# SparkFun_GPS_RTK_Surveyor_-_Single_End.net
KiCad netlist of a schematic drawn in EAGLE
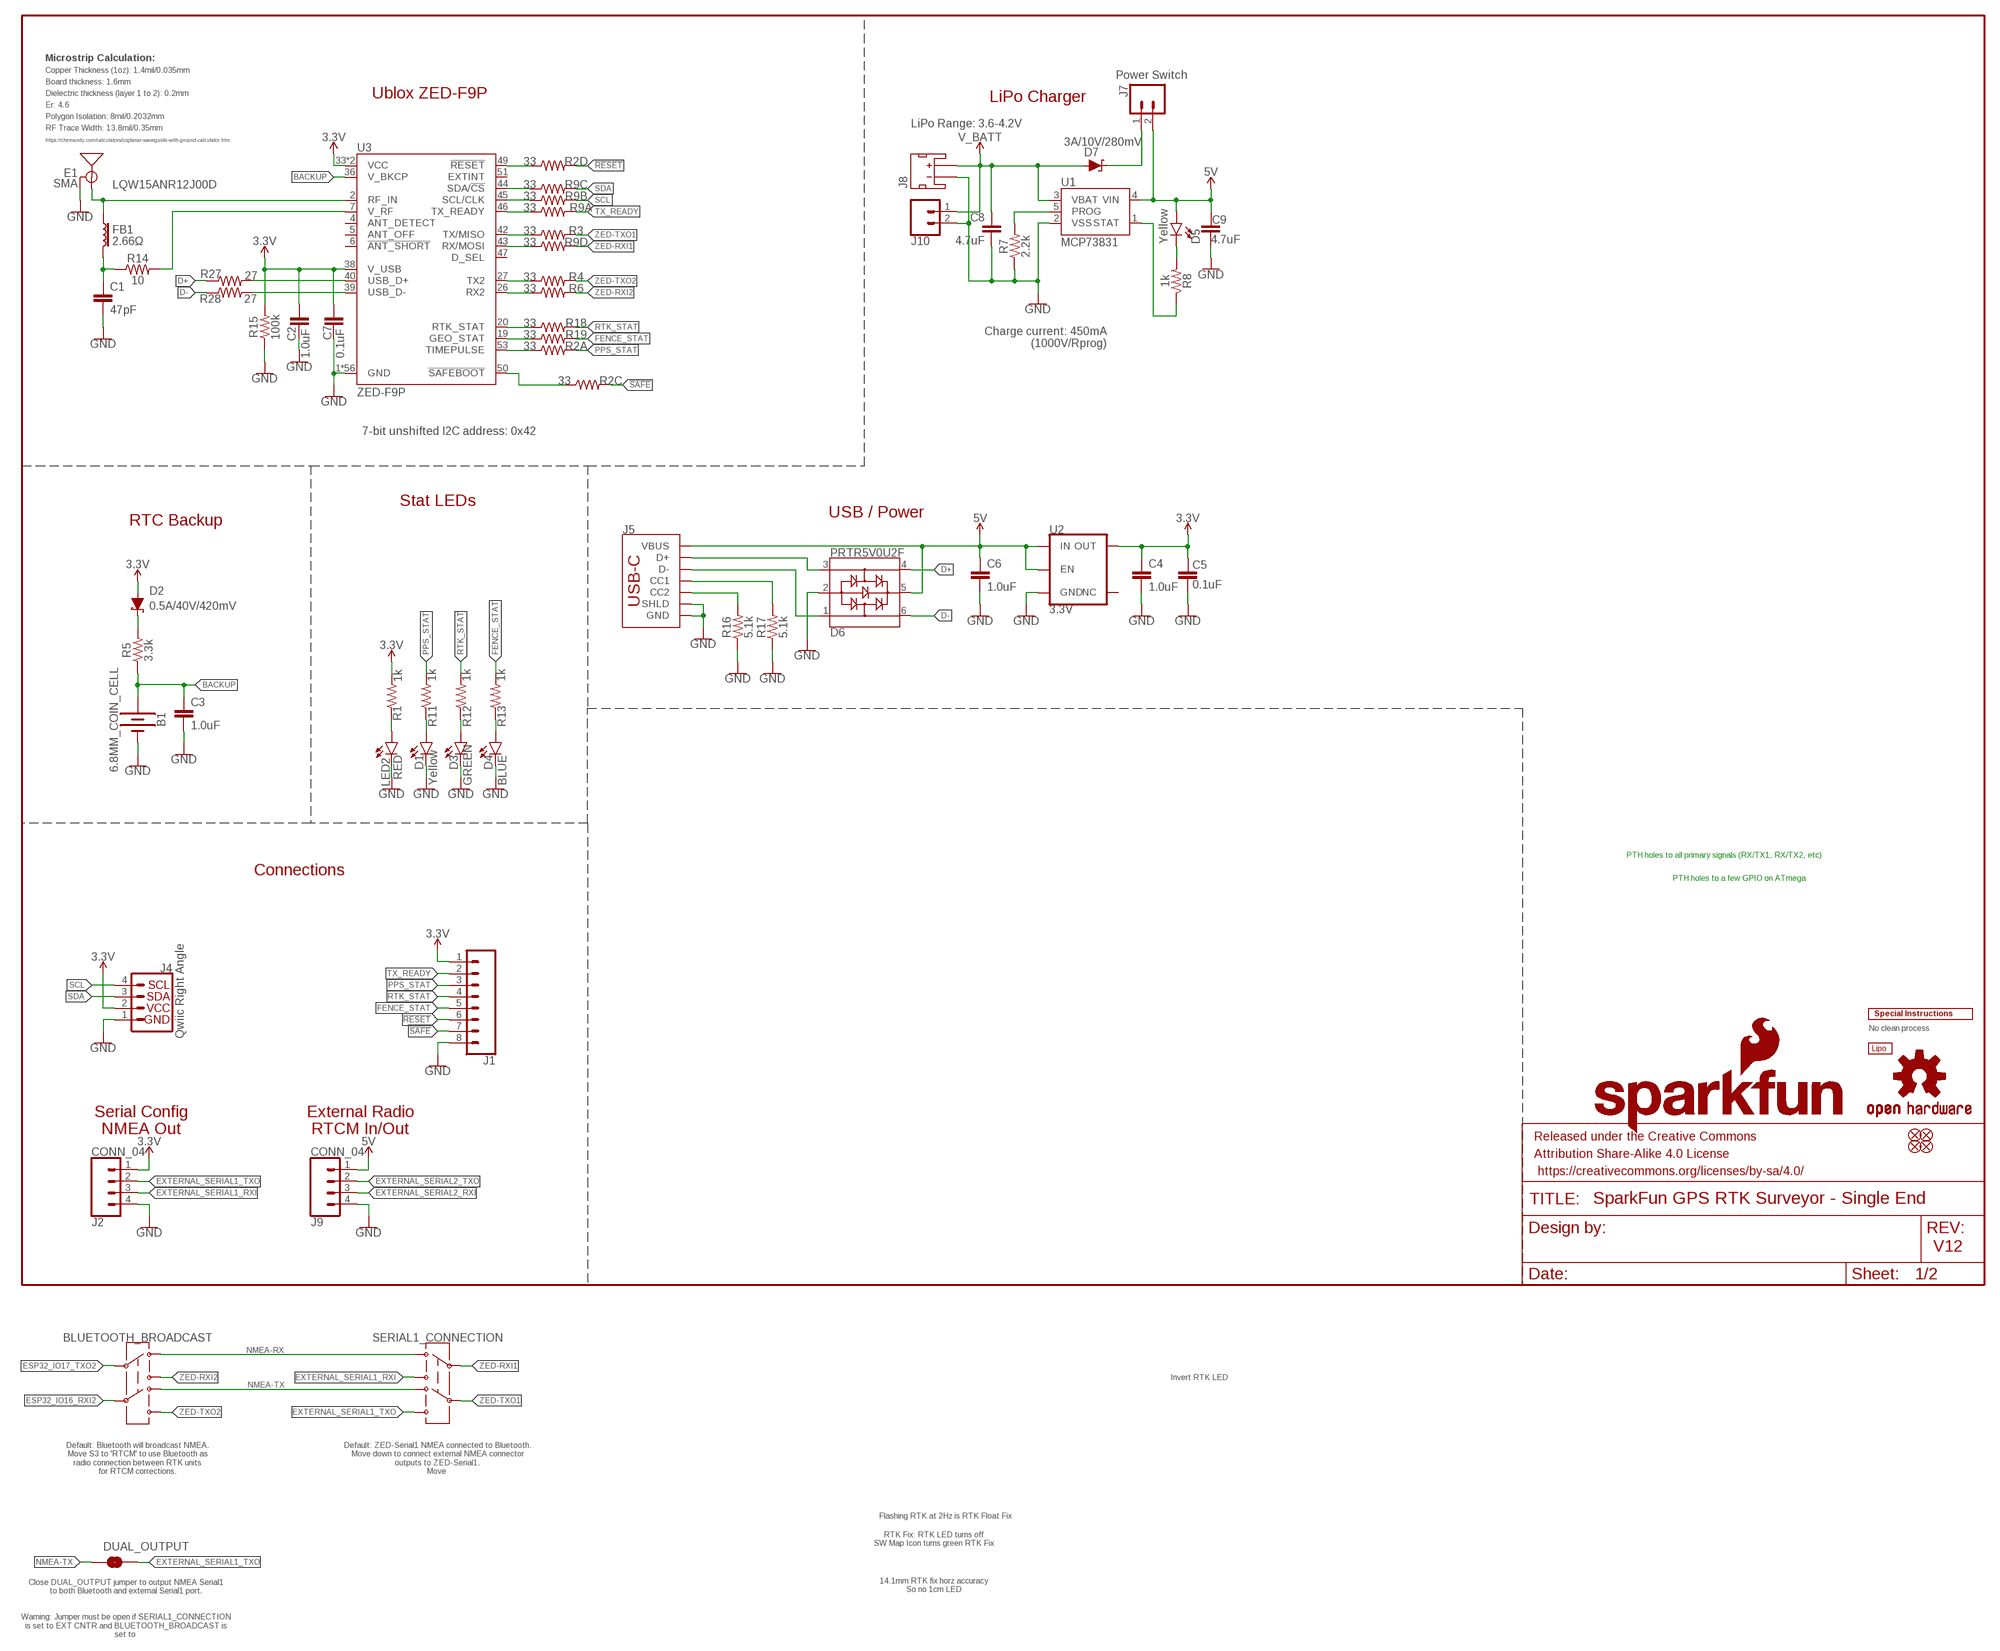
[diagram p0: schematic, sheet 1, part 1 of 2]
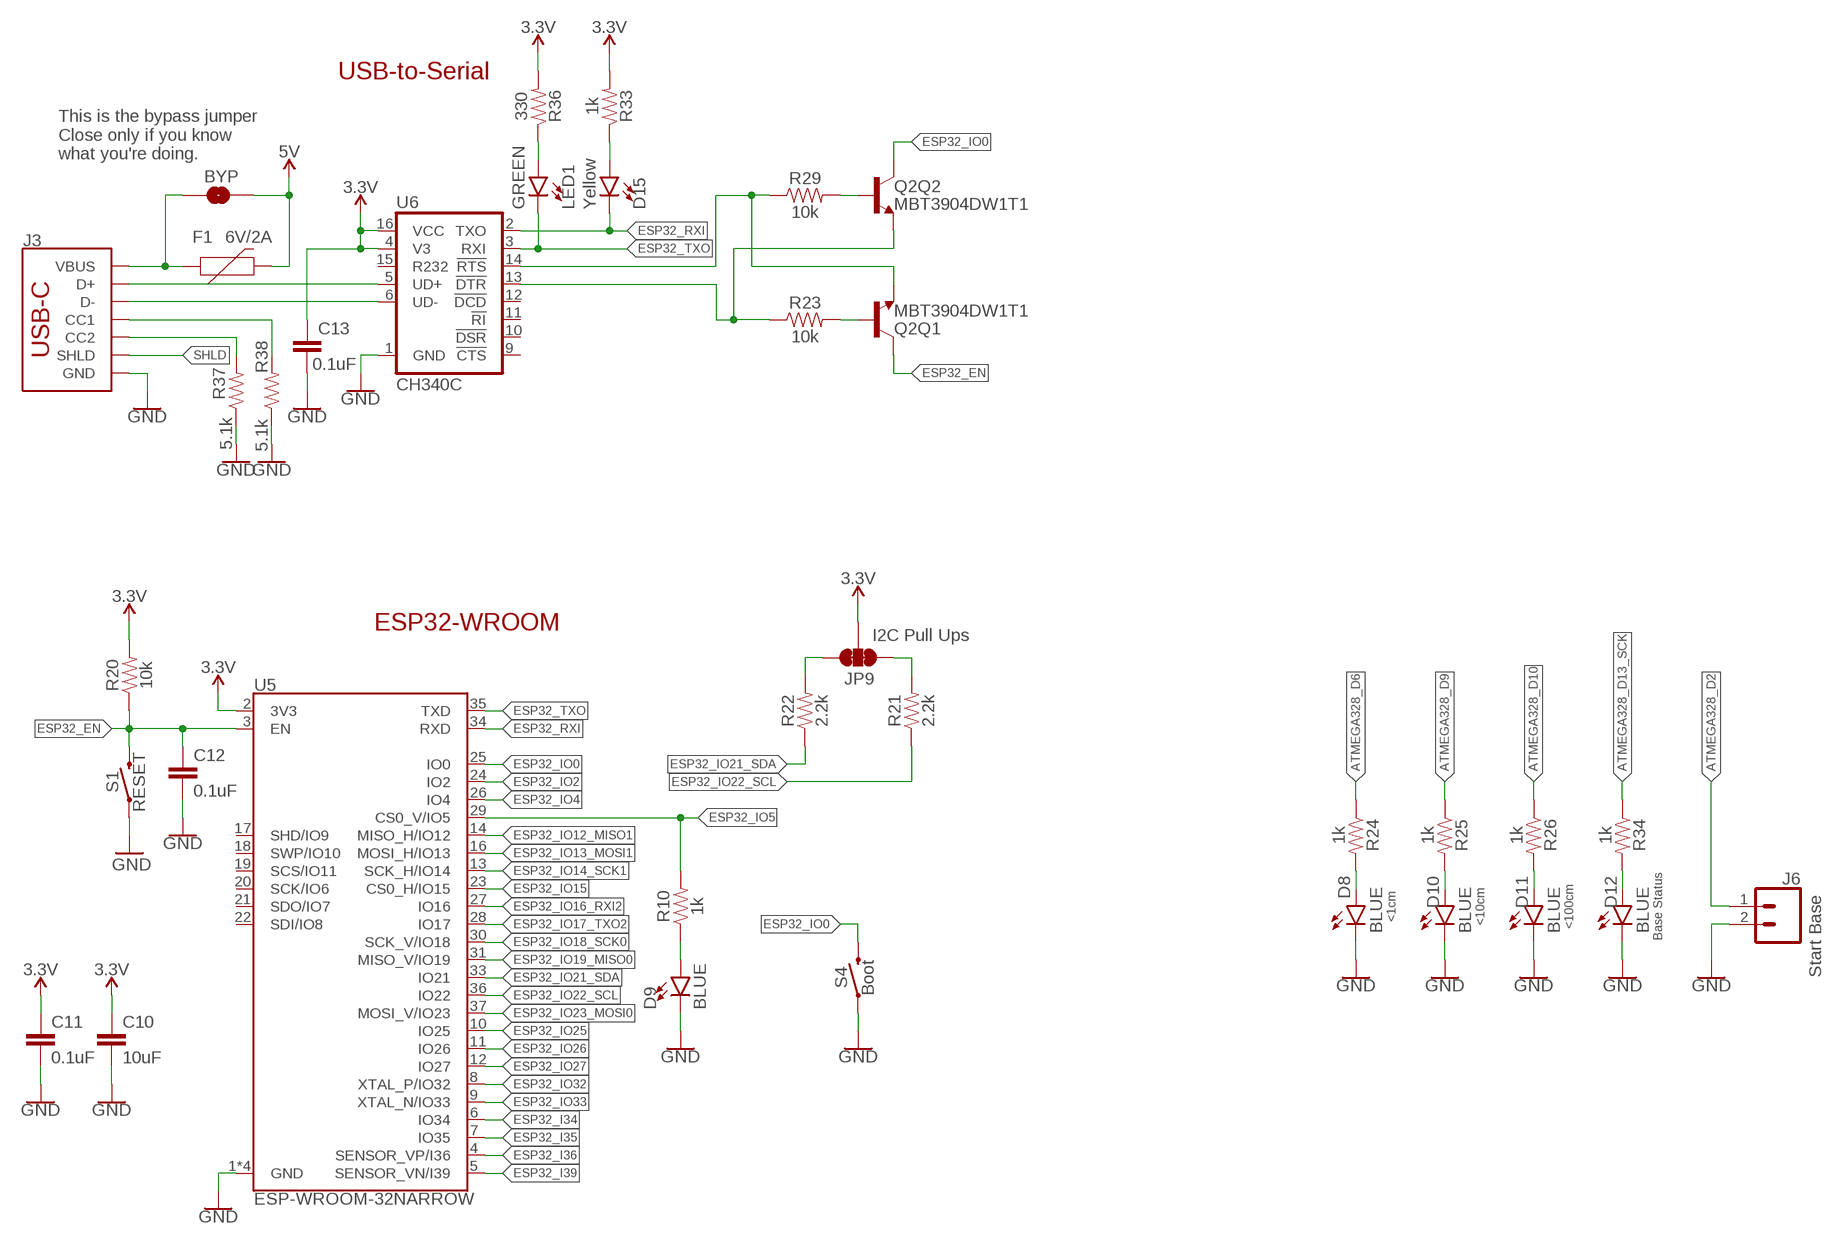
[diagram p1: schematic, sheet 1, part 2 of 2]

(export (version "E")
  (design (tool "Eeschema 10.0.6"))
  (components
    (comp (ref "B1")
      (value "6.8MM_COIN_CELL")
      (footprint "eagle-import:ML414H_IV01E")
      (libsource (lib "eagle-import") (part "ML414H_IV01E_BATTERY"))
    )
    (comp (ref "BLUETOOTH_BROADCAST")
      (value "SWITCH-DPDT-SMD-AYZ0202")
      (footprint "eagle-import:SWITCH_DPDT_SMD_AYZ0202")
      (libsource (lib "eagle-import") (part "SWITCH-DPDT-SMD-AYZ0202"))
    )
    (comp (ref "BT1")
      (value "LIPO-OUTLINE1100")
      (footprint "eagle-import:LIPO-1000")
      (libsource (lib "eagle-import") (part "LIPO-OUTLINE1100"))
    )
    (comp (ref "BYP")
      (value "JUMPER-SMT_2_NO_SILK")
      (footprint "eagle-import:SMT-JUMPER_2_NO_SILK")
      (libsource (lib "eagle-import") (part "JUMPER-SMT_2_NO_SILK"))
    )
    (comp (ref "C1")
      (value "47pF")
      (footprint "eagle-import:0402")
      (libsource (lib "eagle-import") (part "47PF-0402-25V-5%-X7R"))
    )
    (comp (ref "C2")
      (value "1.0uF")
      (footprint "eagle-import:0603")
      (libsource (lib "eagle-import") (part "1.0UF-0603-16V-10%-X7R"))
    )
    (comp (ref "C3")
      (value "1.0uF")
      (footprint "eagle-import:0603")
      (libsource (lib "eagle-import") (part "1.0UF-0603-16V-10%-X7R"))
    )
    (comp (ref "C4")
      (value "1.0uF")
      (footprint "eagle-import:0603")
      (libsource (lib "eagle-import") (part "1.0UF-0603-16V-10%-X7R"))
    )
    (comp (ref "C5")
      (value "0.1uF")
      (footprint "eagle-import:0603")
      (libsource (lib "eagle-import") (part "0.1UF-0603-25V-5%"))
    )
    (comp (ref "C6")
      (value "1.0uF")
      (footprint "eagle-import:0603")
      (libsource (lib "eagle-import") (part "1.0UF-0603-16V-10%-X7R"))
    )
    (comp (ref "C7")
      (value "0.1uF")
      (footprint "eagle-import:0603")
      (libsource (lib "eagle-import") (part "0.1UF-0603-25V-5%"))
    )
    (comp (ref "C8")
      (value "4.7uF")
      (footprint "eagle-import:0603")
      (libsource (lib "eagle-import") (part "4.7UF-0603-35V-(20%)"))
    )
    (comp (ref "C9")
      (value "4.7uF")
      (footprint "eagle-import:0603")
      (libsource (lib "eagle-import") (part "4.7UF-0603-35V-(20%)"))
    )
    (comp (ref "C10")
      (value "10uF")
      (footprint "eagle-import:0603")
      (libsource (lib "eagle-import") (part "10UF-0603-6.3V-20%"))
    )
    (comp (ref "C11")
      (value "0.1uF")
      (footprint "eagle-import:0603")
      (libsource (lib "eagle-import") (part "0.1UF-0603-25V-(+80/-20%)"))
    )
    (comp (ref "C12")
      (value "0.1uF")
      (footprint "eagle-import:0603")
      (libsource (lib "eagle-import") (part "0.1UF-0603-25V-(+80/-20%)"))
    )
    (comp (ref "C13")
      (value "0.1uF")
      (footprint "eagle-import:0603")
      (libsource (lib "eagle-import") (part "0.1UF-0603-25V-(+80/-20%)"))
    )
    (comp (ref "D1")
      (value "Yellow")
      (footprint "eagle-import:LED-0603")
      (libsource (lib "eagle-import") (part "LED-YELLOW0603"))
    )
    (comp (ref "D2")
      (value "0.5A/40V/420mV")
      (footprint "eagle-import:SOD-323")
      (libsource (lib "eagle-import") (part "DIODE-SCHOTTKY-PMEG4005EJ"))
    )
    (comp (ref "D3")
      (value "GREEN")
      (footprint "eagle-import:LED-0603")
      (libsource (lib "eagle-import") (part "LED-GREEN0603"))
    )
    (comp (ref "D4")
      (value "BLUE")
      (footprint "eagle-import:LED-0603")
      (libsource (lib "eagle-import") (part "LED-BLUE0603"))
    )
    (comp (ref "D5")
      (value "Yellow")
      (footprint "eagle-import:LED-0603")
      (libsource (lib "eagle-import") (part "LED-YELLOW0603"))
    )
    (comp (ref "D6")
      (value "PRTR5V0U2F")
      (footprint "eagle-import:SOT886")
      (libsource (lib "eagle-import") (part "PRTR5V0U2F"))
    )
    (comp (ref "D7")
      (value "3A/10V/280mV")
      (footprint "eagle-import:SOD-323")
      (libsource (lib "eagle-import") (part "DIODE-SCHOTTKY-BAT60A"))
    )
    (comp (ref "D8")
      (value "BLUE")
      (footprint "eagle-import:LED-0603")
      (libsource (lib "eagle-import") (part "LED-BLUE0603"))
    )
    (comp (ref "D9")
      (value "BLUE")
      (footprint "eagle-import:LED-0603")
      (libsource (lib "eagle-import") (part "LED-BLUE0603"))
    )
    (comp (ref "D10")
      (value "BLUE")
      (footprint "eagle-import:LED-0603")
      (libsource (lib "eagle-import") (part "LED-BLUE0603"))
    )
    (comp (ref "D11")
      (value "BLUE")
      (footprint "eagle-import:LED-0603")
      (libsource (lib "eagle-import") (part "LED-BLUE0603"))
    )
    (comp (ref "D12")
      (value "BLUE")
      (footprint "eagle-import:LED-0603")
      (libsource (lib "eagle-import") (part "LED-BLUE0603"))
    )
    (comp (ref "D15")
      (value "Yellow")
      (footprint "eagle-import:LED-0603")
      (libsource (lib "eagle-import") (part "LED-YELLOW0603"))
    )
    (comp (ref "DUAL_OUTPUT")
      (value "JUMPER-SMT_2_NO_SILK")
      (footprint "eagle-import:SMT-JUMPER_2_NO_SILK")
      (libsource (lib "eagle-import") (part "JUMPER-SMT_2_NO_SILK"))
    )
    (comp (ref "E1")
      (value "SMA")
      (footprint "eagle-import:SMA-EDGE-SMD")
      (libsource (lib "eagle-import") (part "ANTENNA-GROUNDEDEDGE_SMA_SMD"))
    )
    (comp (ref "F1")
      (value "6V/2A")
      (footprint "eagle-import:1210")
      (libsource (lib "eagle-import") (part "PPTC_6V2A"))
    )
    (comp (ref "FB1")
      (value "2.66Ω")
      (footprint "eagle-import:0402-TIGHT")
      (libsource (lib "eagle-import") (part "FERRITE_BEAD-0402-2.66OHM-1GHZ"))
    )
    (comp (ref "FRAME2")
      (value "FRAME-LEDGER")
      (footprint "eagle-import:CREATIVE_COMMONS")
      (libsource (lib "eagle-import") (part "FRAME-LEDGER"))
    )
    (comp (ref "J1")
      (value "CONN_08NO_SILK_DNP")
      (footprint "eagle-import:1X08_NO_SILK")
      (libsource (lib "eagle-import") (part "CONN_08NO_SILK_DNP"))
    )
    (comp (ref "J2")
      (value "CONN_04")
      (footprint "eagle-import:JST-4-SMD-1.25MM-LOCKING")
      (libsource (lib "eagle-import") (part "CONN_04"))
    )
    (comp (ref "J3")
      (value "USB-C")
      (footprint "eagle-import:USB-C-16P-2LAYER-PADS")
      (libsource (lib "eagle-import") (part "USB_C_2-LAYER_PADS"))
    )
    (comp (ref "J4")
      (value "Qwiic Right Angle")
      (footprint "eagle-import:JST04_1MM_RA")
      (libsource (lib "eagle-import") (part "I2C_STANDARDQWIIC"))
    )
    (comp (ref "J5")
      (value "USB_C_2-LAYER_PADS")
      (footprint "eagle-import:USB-C-16P-2LAYER-PADS")
      (libsource (lib "eagle-import") (part "USB_C_2-LAYER_PADS"))
    )
    (comp (ref "J6")
      (value "Start Base")
      (footprint "eagle-import:JST-2-SMD")
      (libsource (lib "eagle-import") (part "CONN_02-JST-2MM-SMT"))
    )
    (comp (ref "J7")
      (value "Power Switch")
      (footprint "eagle-import:JST-2-SMD")
      (libsource (lib "eagle-import") (part "CONN_02-JST-2MM-SMT"))
    )
    (comp (ref "J8")
      (value "JST_2MM_MALE")
      (footprint "eagle-import:JST-2-SMD")
      (libsource (lib "eagle-import") (part "JST_2MM_MALE"))
    )
    (comp (ref "J9")
      (value "CONN_04")
      (footprint "eagle-import:JST-4-SMD-1.25MM-LOCKING")
      (libsource (lib "eagle-import") (part "CONN_04"))
    )
    (comp (ref "J10")
      (value "CONN_021X02_NO_SILK")
      (footprint "eagle-import:1X02_NO_SILK")
      (libsource (lib "eagle-import") (part "CONN_021X02_NO_SILK"))
    )
    (comp (ref "JP9")
      (value "JUMPER-SMT_3_2-NC_TRACE_SILK")
      (footprint "eagle-import:SMT-JUMPER_3_2-NC_TRACE_SILK")
      (libsource (lib "eagle-import") (part "JUMPER-SMT_3_2-NC_TRACE_SILK"))
    )
    (comp (ref "JP21")
      (value "FIDUCIALUFIDUCIAL")
      (footprint "eagle-import:MICRO-FIDUCIAL")
      (libsource (lib "eagle-import") (part "FIDUCIALUFIDUCIAL"))
    )
    (comp (ref "JP61")
      (value "FIDUCIALUFIDUCIAL")
      (footprint "eagle-import:MICRO-FIDUCIAL")
      (libsource (lib "eagle-import") (part "FIDUCIALUFIDUCIAL"))
    )
    (comp (ref "JP71")
      (value "FIDUCIALUFIDUCIAL")
      (footprint "eagle-import:MICRO-FIDUCIAL")
      (libsource (lib "eagle-import") (part "FIDUCIALUFIDUCIAL"))
    )
    (comp (ref "JP81")
      (value "FIDUCIALUFIDUCIAL")
      (footprint "eagle-import:MICRO-FIDUCIAL")
      (libsource (lib "eagle-import") (part "FIDUCIALUFIDUCIAL"))
    )
    (comp (ref "LED1")
      (value "GREEN")
      (footprint "eagle-import:LED-0603")
      (libsource (lib "eagle-import") (part "LED-GREEN0603"))
    )
    (comp (ref "LED2")
      (value "RED")
      (footprint "eagle-import:LED-0603")
      (libsource (lib "eagle-import") (part "LED-RED0603"))
    )
    (comp (ref "LOGO1")
      (value "OSHW-LOGOMINI")
      (footprint "eagle-import:OSHW-LOGO-MINI")
      (libsource (lib "eagle-import") (part "OSHW-LOGOMINI"))
    )
    (comp (ref "LOGO2")
      (value "SFE_LOGO_NAME_FLAME.1_INCH")
      (footprint "eagle-import:SFE_LOGO_NAME_FLAME_.1")
      (libsource (lib "eagle-import") (part "SFE_LOGO_NAME_FLAME.1_INCH"))
    )
    (comp (ref "Q2")
      (value "MBT3904DW1T1")
      (footprint "eagle-import:SC70-6")
      (libsource (lib "eagle-import") (part "TRANS_NPN_DUAL-MBT3904DW1T1"))
    )
    (comp (ref "R1")
      (value "1k")
      (footprint "eagle-import:0603")
      (libsource (lib "eagle-import") (part "1KOHM-0603-1/10W-1%"))
    )
    (comp (ref "R2")
      (value "33")
      (footprint "eagle-import:1206_RA")
      (libsource (lib "eagle-import") (part "33OHM_RA-1206-1/16W-5%"))
    )
    (comp (ref "R3")
      (value "33")
      (footprint "eagle-import:0603")
      (libsource (lib "eagle-import") (part "33OHM-0603-1/10W-1%"))
    )
    (comp (ref "R4")
      (value "33")
      (footprint "eagle-import:0603")
      (libsource (lib "eagle-import") (part "33OHM-0603-1/10W-1%"))
    )
    (comp (ref "R5")
      (value "3.3k")
      (footprint "eagle-import:0603")
      (libsource (lib "eagle-import") (part "3.3KOHM-0603-1/10W-1%"))
    )
    (comp (ref "R6")
      (value "33")
      (footprint "eagle-import:0603")
      (libsource (lib "eagle-import") (part "33OHM-0603-1/10W-1%"))
    )
    (comp (ref "R7")
      (value "2.2k")
      (footprint "eagle-import:0603")
      (libsource (lib "eagle-import") (part "2.2KOHM-0603-1/10W-1%"))
    )
    (comp (ref "R8")
      (value "1k")
      (footprint "eagle-import:0603")
      (libsource (lib "eagle-import") (part "1KOHM-0603-1/10W-1%"))
    )
    (comp (ref "R9")
      (value "33")
      (footprint "eagle-import:1206_RA")
      (libsource (lib "eagle-import") (part "33OHM_RA-1206-1/16W-5%"))
    )
    (comp (ref "R10")
      (value "1k")
      (footprint "eagle-import:0603")
      (libsource (lib "eagle-import") (part "1KOHM-0603-1/10W-1%"))
    )
    (comp (ref "R11")
      (value "1k")
      (footprint "eagle-import:0603")
      (libsource (lib "eagle-import") (part "1KOHM-0603-1/10W-1%"))
    )
    (comp (ref "R12")
      (value "1k")
      (footprint "eagle-import:0603")
      (libsource (lib "eagle-import") (part "1KOHM-0603-1/10W-1%"))
    )
    (comp (ref "R13")
      (value "1k")
      (footprint "eagle-import:0603")
      (libsource (lib "eagle-import") (part "1KOHM-0603-1/10W-1%"))
    )
    (comp (ref "R14")
      (value "10")
      (footprint "eagle-import:0603")
      (libsource (lib "eagle-import") (part "10OHM-0603-1/10W-1%"))
    )
    (comp (ref "R15")
      (value "100k")
      (footprint "eagle-import:0603")
      (libsource (lib "eagle-import") (part "100KOHM-0603-1/10W-1%"))
    )
    (comp (ref "R16")
      (value "5.1k")
      (footprint "eagle-import:0603")
      (libsource (lib "eagle-import") (part "5.1KOHM5.1KOHM-0603-1/10W-1%"))
    )
    (comp (ref "R17")
      (value "5.1k")
      (footprint "eagle-import:0603")
      (libsource (lib "eagle-import") (part "5.1KOHM5.1KOHM-0603-1/10W-1%"))
    )
    (comp (ref "R18")
      (value "33")
      (footprint "eagle-import:0603")
      (libsource (lib "eagle-import") (part "33OHM-0603-1/10W-1%"))
    )
    (comp (ref "R19")
      (value "33")
      (footprint "eagle-import:0603")
      (libsource (lib "eagle-import") (part "33OHM-0603-1/10W-1%"))
    )
    (comp (ref "R20")
      (value "10k")
      (footprint "eagle-import:0603")
      (libsource (lib "eagle-import") (part "10KOHM-0603-1/10W-1%"))
    )
    (comp (ref "R21")
      (value "2.2k")
      (footprint "eagle-import:0603")
      (libsource (lib "eagle-import") (part "2.2KOHM-0603-1/10W-1%"))
    )
    (comp (ref "R22")
      (value "2.2k")
      (footprint "eagle-import:0603")
      (libsource (lib "eagle-import") (part "2.2KOHM-0603-1/10W-1%"))
    )
    (comp (ref "R23")
      (value "10k")
      (footprint "eagle-import:0603")
      (libsource (lib "eagle-import") (part "10KOHM-0603-1/10W-1%"))
    )
    (comp (ref "R24")
      (value "1k")
      (footprint "eagle-import:0603")
      (libsource (lib "eagle-import") (part "1KOHM-0603-1/10W-1%"))
    )
    (comp (ref "R25")
      (value "1k")
      (footprint "eagle-import:0603")
      (libsource (lib "eagle-import") (part "1KOHM-0603-1/10W-1%"))
    )
    (comp (ref "R26")
      (value "1k")
      (footprint "eagle-import:0603")
      (libsource (lib "eagle-import") (part "1KOHM-0603-1/10W-1%"))
    )
    (comp (ref "R27")
      (value "27")
      (footprint "eagle-import:0603")
      (libsource (lib "eagle-import") (part "27OHM-0603-1/10W-1%"))
    )
    (comp (ref "R28")
      (value "27")
      (footprint "eagle-import:0603")
      (libsource (lib "eagle-import") (part "27OHM-0603-1/10W-1%"))
    )
    (comp (ref "R29")
      (value "10k")
      (footprint "eagle-import:0603")
      (libsource (lib "eagle-import") (part "10KOHM-0603-1/10W-1%"))
    )
    (comp (ref "R33")
      (value "1k")
      (footprint "eagle-import:0603")
      (libsource (lib "eagle-import") (part "1KOHM-0603-1/10W-1%"))
    )
    (comp (ref "R34")
      (value "1k")
      (footprint "eagle-import:0603")
      (libsource (lib "eagle-import") (part "1KOHM-0603-1/10W-1%"))
    )
    (comp (ref "R36")
      (value "330")
      (footprint "eagle-import:0603")
      (libsource (lib "eagle-import") (part "330OHM-0603-1/10W-1%"))
    )
    (comp (ref "R37")
      (value "5.1k")
      (footprint "eagle-import:0603")
      (libsource (lib "eagle-import") (part "5.1KOHM5.1KOHM-0603-1/10W-1%"))
    )
    (comp (ref "R38")
      (value "5.1k")
      (footprint "eagle-import:0603")
      (libsource (lib "eagle-import") (part "5.1KOHM5.1KOHM-0603-1/10W-1%"))
    )
    (comp (ref "S1")
      (value "RESET")
      (footprint "eagle-import:TACTILE_SWITCH_SMD_6.0X3.5MM")
      (libsource (lib "eagle-import") (part "MOMENTARY-SWITCH-SPST-SMD-6.0X3.5MM"))
    )
    (comp (ref "S4")
      (value "Boot")
      (footprint "eagle-import:TACTILE_SWITCH_SMD_6.0X3.5MM")
      (libsource (lib "eagle-import") (part "MOMENTARY-SWITCH-SPST-SMD-6.0X3.5MM"))
    )
    (comp (ref "SERIAL1_CONNECTION")
      (value "SWITCH-DPDT-SMD-AYZ0202")
      (footprint "eagle-import:SWITCH_DPDT_SMD_AYZ0202")
      (libsource (lib "eagle-import") (part "SWITCH-DPDT-SMD-AYZ0202"))
    )
    (comp (ref "U$2")
      (value "SPECIAL_INSTRUCTIONS-ORDERING")
      (footprint "eagle-import:ORDERING_INSTRUCTIONS")
      (libsource (lib "eagle-import") (part "SPECIAL_INSTRUCTIONS-ORDERING"))
    )
    (comp (ref "U1")
      (value "MCP73831")
      (footprint "eagle-import:SOT23-5")
      (libsource (lib "eagle-import") (part "MCP73831"))
    )
    (comp (ref "U2")
      (value "3.3V")
      (footprint "eagle-import:SOT23-5")
      (libsource (lib "eagle-import") (part "V_REG_AP2112K-3.3V"))
    )
    (comp (ref "U3")
      (value "ZED-F9P")
      (footprint "eagle-import:ZED-F9P")
      (libsource (lib "eagle-import") (part "ZED-F9P"))
    )
    (comp (ref "U5")
      (value "ESP-WROOM-32NARROW")
      (footprint "eagle-import:ESP-WROOM-32-NARROW")
      (libsource (lib "eagle-import") (part "ESP-WROOM-32NARROW"))
    )
    (comp (ref "U6")
      (value "CH340C")
      (footprint "eagle-import:SO016")
      (libsource (lib "eagle-import") (part "CH340C"))
    )
  )
  (nets
    (net (code "1") (name "3.3V") (class "Default")
      (node (ref "C10") (pin "1") (pinfunction "1_1") (pintype "passive"))
      (node (ref "C11") (pin "1") (pinfunction "1_1") (pintype "passive"))
      (node (ref "C13") (pin "1") (pinfunction "1_1") (pintype "passive"))
      (node (ref "C2") (pin "1") (pinfunction "1_1") (pintype "passive"))
      (node (ref "C4") (pin "1") (pinfunction "1_1") (pintype "passive"))
      (node (ref "C5") (pin "2") (pinfunction "2_2") (pintype "passive"))
      (node (ref "C7") (pin "2") (pinfunction "2_2") (pintype "passive"))
      (node (ref "D2") (pin "A") (pinfunction "A_A") (pintype "passive"))
      (node (ref "J1") (pin "1") (pinfunction "1_1") (pintype "passive"))
      (node (ref "J2") (pin "1") (pinfunction "1_1") (pintype "passive"))
      (node (ref "J4") (pin "2") (pinfunction "2_2") (pintype "power_in"))
      (node (ref "JP9") (pin "2") (pinfunction "2_2") (pintype "passive"))
      (node (ref "R1") (pin "2") (pinfunction "2_2") (pintype "passive"))
      (node (ref "R15") (pin "2") (pinfunction "2_2") (pintype "passive"))
      (node (ref "R20") (pin "2") (pinfunction "2_2") (pintype "passive"))
      (node (ref "R33") (pin "2") (pinfunction "2_2") (pintype "passive"))
      (node (ref "R36") (pin "2") (pinfunction "2_2") (pintype "passive"))
      (node (ref "U2") (pin "5") (pinfunction "OUT_5") (pintype "passive"))
      (node (ref "U3") (pin "33") (pinfunction "VCC_33") (pintype "bidirectional"))
      (node (ref "U3") (pin "34") (pinfunction "VCC_34") (pintype "bidirectional"))
      (node (ref "U3") (pin "38") (pinfunction "V_USB_38") (pintype "bidirectional"))
      (node (ref "U5") (pin "2") (pinfunction "3V3_2") (pintype "bidirectional"))
      (node (ref "U6") (pin "16") (pinfunction "VCC_16") (pintype "bidirectional"))
      (node (ref "U6") (pin "4") (pinfunction "V3_4") (pintype "bidirectional"))
    )
    (net (code "2") (name "5V") (class "Default")
      (node (ref "BYP") (pin "2") (pinfunction "2_2") (pintype "passive"))
      (node (ref "C6") (pin "1") (pinfunction "1_1") (pintype "passive"))
      (node (ref "C9") (pin "1") (pinfunction "1_1") (pintype "passive"))
      (node (ref "D5") (pin "A") (pinfunction "A_A") (pintype "passive"))
      (node (ref "D6") (pin "5") (pinfunction "5_5") (pintype "bidirectional"))
      (node (ref "F1") (pin "2") (pinfunction "2_2") (pintype "bidirectional"))
      (node (ref "J5") (pin "VBUS1") (pinfunction "VBUS_VBUS1") (pintype "bidirectional"))
      (node (ref "J5") (pin "VBUS2") (pinfunction "VBUS_VBUS2") (pintype "bidirectional"))
      (node (ref "J7") (pin "2") (pinfunction "1_2") (pintype "passive"))
      (node (ref "J9") (pin "1") (pinfunction "1_1") (pintype "passive"))
      (node (ref "U1") (pin "4") (pinfunction "VIN_4") (pintype "power_in"))
      (node (ref "U2") (pin "1") (pinfunction "IN_1") (pintype "input"))
      (node (ref "U2") (pin "3") (pinfunction "EN_3") (pintype "input"))
    )
    (net (code "3") (name "ATMEGA328_D2") (class "Default")
      (node (ref "J6") (pin "1") (pinfunction "2_1") (pintype "passive"))
    )
    (net (code "4") (name "ATMEGA328_D6") (class "Default")
      (node (ref "R24") (pin "1") (pinfunction "1_1") (pintype "passive"))
    )
    (net (code "5") (name "ATMEGA328_D9") (class "Default")
      (node (ref "R25") (pin "1") (pinfunction "1_1") (pintype "passive"))
    )
    (net (code "6") (name "ATMEGA328_D10") (class "Default")
      (node (ref "R26") (pin "1") (pinfunction "1_1") (pintype "passive"))
    )
    (net (code "7") (name "ATMEGA328_D13_SCK") (class "Default")
      (node (ref "R34") (pin "1") (pinfunction "1_1") (pintype "passive"))
    )
    (net (code "8") (name "BACKUP") (class "Default")
      (node (ref "B1") (pin "+") (pinfunction "+_+") (pintype "power_in"))
      (node (ref "C3") (pin "1") (pinfunction "1_1") (pintype "passive"))
      (node (ref "R5") (pin "1") (pinfunction "1_1") (pintype "passive"))
      (node (ref "U3") (pin "36") (pinfunction "V_BKCP_36") (pintype "bidirectional"))
    )
    (net (code "9") (name "D+") (class "Default")
      (node (ref "D6") (pin "4") (pinfunction "4_4") (pintype "bidirectional"))
      (node (ref "R27") (pin "1") (pinfunction "1_1") (pintype "passive"))
    )
    (net (code "10") (name "D-") (class "Default")
      (node (ref "D6") (pin "6") (pinfunction "6_6") (pintype "bidirectional"))
      (node (ref "R28") (pin "1") (pinfunction "1_1") (pintype "passive"))
    )
    (net (code "11") (name "ESP32_EN") (class "Default")
      (node (ref "C12") (pin "1") (pinfunction "1_1") (pintype "passive"))
      (node (ref "Q2") (pin "3") (pinfunction "C_3") (pintype "passive"))
      (node (ref "R20") (pin "1") (pinfunction "1_1") (pintype "passive"))
      (node (ref "S1") (pin "2") (pinfunction "2_2") (pintype "passive"))
      (node (ref "U5") (pin "3") (pinfunction "EN_3") (pintype "bidirectional"))
    )
    (net (code "12") (name "ESP32_I34") (class "Default")
      (node (ref "U5") (pin "6") (pinfunction "IO34_6") (pintype "bidirectional"))
    )
    (net (code "13") (name "ESP32_I35") (class "Default")
      (node (ref "U5") (pin "7") (pinfunction "IO35_7") (pintype "bidirectional"))
    )
    (net (code "14") (name "ESP32_I36") (class "Default")
      (node (ref "U5") (pin "4") (pinfunction "SENSOR_VP/I36_4") (pintype "bidirectional"))
    )
    (net (code "15") (name "ESP32_I39") (class "Default")
      (node (ref "U5") (pin "5") (pinfunction "SENSOR_VN/I39_5") (pintype "bidirectional"))
    )
    (net (code "16") (name "ESP32_IO0") (class "Default")
      (node (ref "Q2") (pin "6") (pinfunction "C_6") (pintype "passive"))
      (node (ref "S4") (pin "2") (pinfunction "2_2") (pintype "passive"))
      (node (ref "U5") (pin "25") (pinfunction "IO0_25") (pintype "bidirectional"))
    )
    (net (code "17") (name "ESP32_IO2") (class "Default")
      (node (ref "U5") (pin "24") (pinfunction "IO2_24") (pintype "bidirectional"))
    )
    (net (code "18") (name "ESP32_IO4") (class "Default")
      (node (ref "U5") (pin "26") (pinfunction "IO4_26") (pintype "bidirectional"))
    )
    (net (code "19") (name "ESP32_IO5") (class "Default")
      (node (ref "R10") (pin "2") (pinfunction "2_2") (pintype "passive"))
      (node (ref "U5") (pin "29") (pinfunction "CS0_V/IO5_29") (pintype "bidirectional"))
    )
    (net (code "20") (name "ESP32_IO12_MISO1") (class "Default")
      (node (ref "U5") (pin "14") (pinfunction "MISO_H/IO12_14") (pintype "bidirectional"))
    )
    (net (code "21") (name "ESP32_IO13_MOSI1") (class "Default")
      (node (ref "U5") (pin "16") (pinfunction "MOSI_H/IO13_16") (pintype "bidirectional"))
    )
    (net (code "22") (name "ESP32_IO14_SCK1") (class "Default")
      (node (ref "U5") (pin "13") (pinfunction "SCK_H/IO14_13") (pintype "bidirectional"))
    )
    (net (code "23") (name "ESP32_IO15") (class "Default")
      (node (ref "U5") (pin "23") (pinfunction "CS0_H/IO15_23") (pintype "bidirectional"))
    )
    (net (code "24") (name "ESP32_IO16_RXI2") (class "Default")
      (node (ref "BLUETOOTH_BROADCAST") (pin "5") (pinfunction "5_5") (pintype "bidirectional"))
      (node (ref "U5") (pin "27") (pinfunction "IO16_27") (pintype "bidirectional"))
    )
    (net (code "25") (name "ESP32_IO17_TXO2") (class "Default")
      (node (ref "BLUETOOTH_BROADCAST") (pin "2") (pinfunction "2_2") (pintype "bidirectional"))
      (node (ref "U5") (pin "28") (pinfunction "IO17_28") (pintype "bidirectional"))
    )
    (net (code "26") (name "ESP32_IO18_SCK0") (class "Default")
      (node (ref "U5") (pin "30") (pinfunction "SCK_V/IO18_30") (pintype "bidirectional"))
    )
    (net (code "27") (name "ESP32_IO19_MISO0") (class "Default")
      (node (ref "U5") (pin "31") (pinfunction "MISO_V/IO19_31") (pintype "bidirectional"))
    )
    (net (code "28") (name "ESP32_IO21_SDA") (class "Default")
      (node (ref "R22") (pin "1") (pinfunction "1_1") (pintype "passive"))
      (node (ref "U5") (pin "33") (pinfunction "IO21_33") (pintype "bidirectional"))
    )
    (net (code "29") (name "ESP32_IO22_SCL") (class "Default")
      (node (ref "R21") (pin "1") (pinfunction "1_1") (pintype "passive"))
      (node (ref "U5") (pin "36") (pinfunction "IO22_36") (pintype "bidirectional"))
    )
    (net (code "30") (name "ESP32_IO23_MOSI0") (class "Default")
      (node (ref "U5") (pin "37") (pinfunction "MOSI_V/IO23_37") (pintype "bidirectional"))
    )
    (net (code "31") (name "ESP32_IO25") (class "Default")
      (node (ref "U5") (pin "10") (pinfunction "IO25_10") (pintype "bidirectional"))
    )
    (net (code "32") (name "ESP32_IO26") (class "Default")
      (node (ref "U5") (pin "11") (pinfunction "IO26_11") (pintype "bidirectional"))
    )
    (net (code "33") (name "ESP32_IO27") (class "Default")
      (node (ref "U5") (pin "12") (pinfunction "IO27_12") (pintype "bidirectional"))
    )
    (net (code "34") (name "ESP32_IO32") (class "Default")
      (node (ref "U5") (pin "8") (pinfunction "XTAL_P/IO32_8") (pintype "bidirectional"))
    )
    (net (code "35") (name "ESP32_IO33") (class "Default")
      (node (ref "U5") (pin "9") (pinfunction "XTAL_N/IO33_9") (pintype "bidirectional"))
    )
    (net (code "36") (name "ESP32_RXI") (class "Default")
      (node (ref "D15") (pin "C") (pinfunction "C_C") (pintype "passive"))
      (node (ref "U5") (pin "34") (pinfunction "RXD_34") (pintype "bidirectional"))
      (node (ref "U6") (pin "2") (pinfunction "TXO_2") (pintype "bidirectional"))
    )
    (net (code "37") (name "ESP32_TXO") (class "Default")
      (node (ref "LED1") (pin "C") (pinfunction "C_C") (pintype "passive"))
      (node (ref "U5") (pin "35") (pinfunction "TXD_35") (pintype "bidirectional"))
      (node (ref "U6") (pin "3") (pinfunction "RXI_3") (pintype "bidirectional"))
    )
    (net (code "38") (name "EXTERNAL_SERIAL1_RXI") (class "Default")
      (node (ref "J2") (pin "3") (pinfunction "3_3") (pintype "passive"))
      (node (ref "SERIAL1_CONNECTION") (pin "3") (pinfunction "3_3") (pintype "bidirectional"))
    )
    (net (code "39") (name "EXTERNAL_SERIAL1_TXO") (class "Default")
      (node (ref "DUAL_OUTPUT") (pin "2") (pinfunction "2_2") (pintype "passive"))
      (node (ref "J2") (pin "2") (pinfunction "2_2") (pintype "passive"))
      (node (ref "SERIAL1_CONNECTION") (pin "6") (pinfunction "6_6") (pintype "bidirectional"))
    )
    (net (code "40") (name "EXTERNAL_SERIAL2_RXI") (class "Default")
      (node (ref "J9") (pin "3") (pinfunction "3_3") (pintype "passive"))
    )
    (net (code "41") (name "EXTERNAL_SERIAL2_TXO") (class "Default")
      (node (ref "J9") (pin "2") (pinfunction "2_2") (pintype "passive"))
    )
    (net (code "42") (name "FENCE_STAT") (class "Default")
      (node (ref "J1") (pin "5") (pinfunction "5_5") (pintype "passive"))
      (node (ref "R13") (pin "2") (pinfunction "2_2") (pintype "passive"))
      (node (ref "R19") (pin "2") (pinfunction "2_2") (pintype "passive"))
    )
    (net (code "43") (name "GND") (class "Default")
      (node (ref "B1") (pin "-") (pinfunction "-_-") (pintype "power_in"))
      (node (ref "C1") (pin "2") (pinfunction "2_2") (pintype "passive"))
      (node (ref "C10") (pin "2") (pinfunction "2_2") (pintype "passive"))
      (node (ref "C11") (pin "2") (pinfunction "2_2") (pintype "passive"))
      (node (ref "C12") (pin "2") (pinfunction "2_2") (pintype "passive"))
      (node (ref "C13") (pin "2") (pinfunction "2_2") (pintype "passive"))
      (node (ref "C2") (pin "2") (pinfunction "2_2") (pintype "passive"))
      (node (ref "C3") (pin "2") (pinfunction "2_2") (pintype "passive"))
      (node (ref "C4") (pin "2") (pinfunction "2_2") (pintype "passive"))
      (node (ref "C5") (pin "1") (pinfunction "1_1") (pintype "passive"))
      (node (ref "C6") (pin "2") (pinfunction "2_2") (pintype "passive"))
      (node (ref "C7") (pin "1") (pinfunction "1_1") (pintype "passive"))
      (node (ref "C8") (pin "2") (pinfunction "2_2") (pintype "passive"))
      (node (ref "C9") (pin "2") (pinfunction "2_2") (pintype "passive"))
      (node (ref "D1") (pin "C") (pinfunction "C_C") (pintype "passive"))
      (node (ref "D10") (pin "C") (pinfunction "C_C") (pintype "passive"))
      (node (ref "D11") (pin "C") (pinfunction "C_C") (pintype "passive"))
      (node (ref "D12") (pin "C") (pinfunction "C_C") (pintype "passive"))
      (node (ref "D3") (pin "C") (pinfunction "C_C") (pintype "passive"))
      (node (ref "D4") (pin "C") (pinfunction "C_C") (pintype "passive"))
      (node (ref "D6") (pin "2") (pinfunction "2_2") (pintype "bidirectional"))
      (node (ref "D8") (pin "C") (pinfunction "C_C") (pintype "passive"))
      (node (ref "D9") (pin "C") (pinfunction "C_C") (pintype "passive"))
      (node (ref "E1") (pin "GND@0") (pinfunction "GND_GND@0") (pintype "bidirectional"))
      (node (ref "E1") (pin "GND@1") (pinfunction "GND_GND@1") (pintype "bidirectional"))
      (node (ref "J1") (pin "8") (pinfunction "8_8") (pintype "passive"))
      (node (ref "J10") (pin "2") (pinfunction "2_2") (pintype "passive"))
      (node (ref "J2") (pin "4") (pinfunction "4_4") (pintype "passive"))
      (node (ref "J3") (pin "GND") (pinfunction "GND_GND") (pintype "bidirectional"))
      (node (ref "J3") (pin "GND2") (pinfunction "GND_GND2") (pintype "bidirectional"))
      (node (ref "J4") (pin "1") (pinfunction "1_1") (pintype "power_in"))
      (node (ref "J5") (pin "GND") (pinfunction "GND_GND") (pintype "bidirectional"))
      (node (ref "J5") (pin "GND2") (pinfunction "GND_GND2") (pintype "bidirectional"))
      (node (ref "J5") (pin "SHLD1") (pinfunction "SHLD_SHLD1") (pintype "bidirectional"))
      (node (ref "J5") (pin "SHLD2") (pinfunction "SHLD_SHLD2") (pintype "bidirectional"))
      (node (ref "J5") (pin "SHLD3") (pinfunction "SHLD_SHLD3") (pintype "bidirectional"))
      (node (ref "J5") (pin "SHLD4") (pinfunction "SHLD_SHLD4") (pintype "bidirectional"))
      (node (ref "J6") (pin "2") (pinfunction "1_2") (pintype "passive"))
      (node (ref "J8") (pin "1") (pinfunction "-_1") (pintype "bidirectional"))
      (node (ref "J9") (pin "4") (pinfunction "4_4") (pintype "passive"))
      (node (ref "LED2") (pin "C") (pinfunction "C_C") (pintype "passive"))
      (node (ref "R15") (pin "1") (pinfunction "1_1") (pintype "passive"))
      (node (ref "R16") (pin "1") (pinfunction "1_1") (pintype "passive"))
      (node (ref "R17") (pin "1") (pinfunction "1_1") (pintype "passive"))
      (node (ref "R37") (pin "1") (pinfunction "1_1") (pintype "passive"))
      (node (ref "R38") (pin "1") (pinfunction "1_1") (pintype "passive"))
      (node (ref "R7") (pin "1") (pinfunction "1_1") (pintype "passive"))
      (node (ref "S1") (pin "1") (pinfunction "1_1") (pintype "passive"))
      (node (ref "S4") (pin "1") (pinfunction "1_1") (pintype "passive"))
      (node (ref "U1") (pin "2") (pinfunction "VSS_2") (pintype "power_in"))
      (node (ref "U2") (pin "2") (pinfunction "GND_2") (pintype "input"))
      (node (ref "U3") (pin "1") (pinfunction "GND_1") (pintype "bidirectional"))
      (node (ref "U3") (pin "100") (pinfunction "GND_100") (pintype "bidirectional"))
      (node (ref "U3") (pin "101") (pinfunction "GND_101") (pintype "bidirectional"))
      (node (ref "U3") (pin "102") (pinfunction "GND_102") (pintype "bidirectional"))
      (node (ref "U3") (pin "12") (pinfunction "GND_12") (pintype "bidirectional"))
      (node (ref "U3") (pin "14") (pinfunction "GND_14") (pintype "bidirectional"))
      (node (ref "U3") (pin "3") (pinfunction "GND_3") (pintype "bidirectional"))
      (node (ref "U3") (pin "32") (pinfunction "GND_32") (pintype "bidirectional"))
      (node (ref "U3") (pin "37") (pinfunction "GND_37") (pintype "bidirectional"))
      (node (ref "U3") (pin "41") (pinfunction "GND_41") (pintype "bidirectional"))
      (node (ref "U3") (pin "48") (pinfunction "GND_48") (pintype "bidirectional"))
      (node (ref "U3") (pin "55") (pinfunction "GND_55") (pintype "bidirectional"))
      (node (ref "U3") (pin "56") (pinfunction "GND_56") (pintype "bidirectional"))
      (node (ref "U3") (pin "57") (pinfunction "GND_57") (pintype "bidirectional"))
      (node (ref "U3") (pin "58") (pinfunction "GND_58") (pintype "bidirectional"))
      (node (ref "U3") (pin "59") (pinfunction "GND_59") (pintype "bidirectional"))
      (node (ref "U3") (pin "60") (pinfunction "GND_60") (pintype "bidirectional"))
      (node (ref "U3") (pin "61") (pinfunction "GND_61") (pintype "bidirectional"))
      (node (ref "U3") (pin "62") (pinfunction "GND_62") (pintype "bidirectional"))
      (node (ref "U3") (pin "63") (pinfunction "GND_63") (pintype "bidirectional"))
      (node (ref "U3") (pin "64") (pinfunction "GND_64") (pintype "bidirectional"))
      (node (ref "U3") (pin "65") (pinfunction "GND_65") (pintype "bidirectional"))
      (node (ref "U3") (pin "66") (pinfunction "GND_66") (pintype "bidirectional"))
      (node (ref "U3") (pin "67") (pinfunction "GND_67") (pintype "bidirectional"))
      (node (ref "U3") (pin "68") (pinfunction "GND_68") (pintype "bidirectional"))
      (node (ref "U3") (pin "69") (pinfunction "GND_69") (pintype "bidirectional"))
      (node (ref "U3") (pin "70") (pinfunction "GND_70") (pintype "bidirectional"))
      (node (ref "U3") (pin "71") (pinfunction "GND_71") (pintype "bidirectional"))
      (node (ref "U3") (pin "72") (pinfunction "GND_72") (pintype "bidirectional"))
      (node (ref "U3") (pin "73") (pinfunction "GND_73") (pintype "bidirectional"))
      (node (ref "U3") (pin "74") (pinfunction "GND_74") (pintype "bidirectional"))
      (node (ref "U3") (pin "75") (pinfunction "GND_75") (pintype "bidirectional"))
      (node (ref "U3") (pin "76") (pinfunction "GND_76") (pintype "bidirectional"))
      (node (ref "U3") (pin "77") (pinfunction "GND_77") (pintype "bidirectional"))
      (node (ref "U3") (pin "78") (pinfunction "GND_78") (pintype "bidirectional"))
      (node (ref "U3") (pin "79") (pinfunction "GND_79") (pintype "bidirectional"))
      (node (ref "U3") (pin "80") (pinfunction "GND_80") (pintype "bidirectional"))
      (node (ref "U3") (pin "81") (pinfunction "GND_81") (pintype "bidirectional"))
      (node (ref "U3") (pin "82") (pinfunction "GND_82") (pintype "bidirectional"))
      (node (ref "U3") (pin "83") (pinfunction "GND_83") (pintype "bidirectional"))
      (node (ref "U3") (pin "84") (pinfunction "GND_84") (pintype "bidirectional"))
      (node (ref "U3") (pin "85") (pinfunction "GND_85") (pintype "bidirectional"))
      (node (ref "U3") (pin "86") (pinfunction "GND_86") (pintype "bidirectional"))
      (node (ref "U3") (pin "87") (pinfunction "GND_87") (pintype "bidirectional"))
      (node (ref "U3") (pin "88") (pinfunction "GND_88") (pintype "bidirectional"))
      (node (ref "U3") (pin "89") (pinfunction "GND_89") (pintype "bidirectional"))
      (node (ref "U3") (pin "90") (pinfunction "GND_90") (pintype "bidirectional"))
      (node (ref "U3") (pin "91") (pinfunction "GND_91") (pintype "bidirectional"))
      (node (ref "U3") (pin "92") (pinfunction "GND_92") (pintype "bidirectional"))
      (node (ref "U3") (pin "93") (pinfunction "GND_93") (pintype "bidirectional"))
      (node (ref "U3") (pin "94") (pinfunction "GND_94") (pintype "bidirectional"))
      (node (ref "U3") (pin "95") (pinfunction "GND_95") (pintype "bidirectional"))
      (node (ref "U3") (pin "96") (pinfunction "GND_96") (pintype "bidirectional"))
      (node (ref "U3") (pin "97") (pinfunction "GND_97") (pintype "bidirectional"))
      (node (ref "U3") (pin "98") (pinfunction "GND_98") (pintype "bidirectional"))
      (node (ref "U3") (pin "99") (pinfunction "GND_99") (pintype "bidirectional"))
      (node (ref "U5") (pin "1") (pinfunction "GND_1") (pintype "bidirectional"))
      (node (ref "U5") (pin "15") (pinfunction "GND_15") (pintype "bidirectional"))
      (node (ref "U5") (pin "38") (pinfunction "GND_38") (pintype "bidirectional"))
      (node (ref "U5") (pin "GND") (pinfunction "GND_GND") (pintype "bidirectional"))
      (node (ref "U6") (pin "1") (pinfunction "GND_1") (pintype "bidirectional"))
    )
    (net (code "44") (name "NMEA-RX") (class "Default")
      (node (ref "BLUETOOTH_BROADCAST") (pin "1") (pinfunction "1_1") (pintype "bidirectional"))
      (node (ref "SERIAL1_CONNECTION") (pin "1") (pinfunction "1_1") (pintype "bidirectional"))
    )
    (net (code "45") (name "NMEA-TX") (class "Default")
      (node (ref "BLUETOOTH_BROADCAST") (pin "4") (pinfunction "4_4") (pintype "bidirectional"))
      (node (ref "DUAL_OUTPUT") (pin "1") (pinfunction "1_1") (pintype "passive"))
      (node (ref "SERIAL1_CONNECTION") (pin "4") (pinfunction "4_4") (pintype "bidirectional"))
    )
    (net (code "46") (name "Net-(BYP-Pad1)") (class "Default")
      (node (ref "BYP") (pin "1") (pinfunction "1_1") (pintype "passive"))
      (node (ref "F1") (pin "1") (pinfunction "1_1") (pintype "bidirectional"))
      (node (ref "J3") (pin "VBUS1") (pinfunction "VBUS_VBUS1") (pintype "bidirectional"))
      (node (ref "J3") (pin "VBUS2") (pinfunction "VBUS_VBUS2") (pintype "bidirectional"))
    )
    (net (code "47") (name "Net-(C1-Pad1)") (class "Default")
      (node (ref "C1") (pin "1") (pinfunction "1_1") (pintype "passive"))
      (node (ref "FB1") (pin "2") (pinfunction "2_2") (pintype "passive"))
      (node (ref "R14") (pin "1") (pinfunction "1_1") (pintype "passive"))
    )
    (net (code "48") (name "Net-(D1-PadA)") (class "Default")
      (node (ref "D1") (pin "A") (pinfunction "A_A") (pintype "passive"))
      (node (ref "R11") (pin "1") (pinfunction "1_1") (pintype "passive"))
    )
    (net (code "49") (name "Net-(D2-PadC)") (class "Default")
      (node (ref "D2") (pin "C") (pinfunction "C_C") (pintype "passive"))
      (node (ref "R5") (pin "2") (pinfunction "2_2") (pintype "passive"))
    )
    (net (code "50") (name "Net-(D3-PadA)") (class "Default")
      (node (ref "D3") (pin "A") (pinfunction "A_A") (pintype "passive"))
      (node (ref "R12") (pin "1") (pinfunction "1_1") (pintype "passive"))
    )
    (net (code "51") (name "Net-(D4-PadA)") (class "Default")
      (node (ref "D4") (pin "A") (pinfunction "A_A") (pintype "passive"))
      (node (ref "R13") (pin "1") (pinfunction "1_1") (pintype "passive"))
    )
    (net (code "52") (name "Net-(D5-PadC)") (class "Default")
      (node (ref "D5") (pin "C") (pinfunction "C_C") (pintype "passive"))
      (node (ref "R8") (pin "2") (pinfunction "2_2") (pintype "passive"))
    )
    (net (code "53") (name "Net-(D6-Pad1)") (class "Default")
      (node (ref "D6") (pin "1") (pinfunction "1_1") (pintype "bidirectional"))
      (node (ref "J5") (pin "A7") (pinfunction "D-_A7") (pintype "bidirectional"))
      (node (ref "J5") (pin "B7") (pinfunction "D-_B7") (pintype "bidirectional"))
    )
    (net (code "54") (name "Net-(D6-Pad3)") (class "Default")
      (node (ref "D6") (pin "3") (pinfunction "3_3") (pintype "bidirectional"))
      (node (ref "J5") (pin "A6") (pinfunction "D+_A6") (pintype "bidirectional"))
      (node (ref "J5") (pin "B6") (pinfunction "D+_B6") (pintype "bidirectional"))
    )
    (net (code "55") (name "Net-(D8-PadA)") (class "Default")
      (node (ref "D8") (pin "A") (pinfunction "A_A") (pintype "passive"))
      (node (ref "R24") (pin "2") (pinfunction "2_2") (pintype "passive"))
    )
    (net (code "56") (name "Net-(D9-PadA)") (class "Default")
      (node (ref "D9") (pin "A") (pinfunction "A_A") (pintype "passive"))
      (node (ref "R10") (pin "1") (pinfunction "1_1") (pintype "passive"))
    )
    (net (code "57") (name "Net-(D10-PadA)") (class "Default")
      (node (ref "D10") (pin "A") (pinfunction "A_A") (pintype "passive"))
      (node (ref "R25") (pin "2") (pinfunction "2_2") (pintype "passive"))
    )
    (net (code "58") (name "Net-(D11-PadA)") (class "Default")
      (node (ref "D11") (pin "A") (pinfunction "A_A") (pintype "passive"))
      (node (ref "R26") (pin "2") (pinfunction "2_2") (pintype "passive"))
    )
    (net (code "59") (name "Net-(D12-PadA)") (class "Default")
      (node (ref "D12") (pin "A") (pinfunction "A_A") (pintype "passive"))
      (node (ref "R34") (pin "2") (pinfunction "2_2") (pintype "passive"))
    )
    (net (code "60") (name "Net-(D15-PadA)") (class "Default")
      (node (ref "D15") (pin "A") (pinfunction "A_A") (pintype "passive"))
      (node (ref "R33") (pin "1") (pinfunction "1_1") (pintype "passive"))
    )
    (net (code "61") (name "Net-(E1-SIGNAL)") (class "Default")
      (node (ref "E1") (pin "SIG") (pinfunction "SIGNAL_SIG") (pintype "bidirectional"))
      (node (ref "FB1") (pin "1") (pinfunction "1_1") (pintype "passive"))
      (node (ref "U3") (pin "2") (pinfunction "RF_IN_2") (pintype "bidirectional"))
    )
    (net (code "62") (name "Net-(J3-CC1)") (class "Default")
      (node (ref "J3") (pin "A5") (pinfunction "CC1_A5") (pintype "bidirectional"))
      (node (ref "R38") (pin "2") (pinfunction "2_2") (pintype "passive"))
    )
    (net (code "63") (name "Net-(J3-CC2)") (class "Default")
      (node (ref "J3") (pin "B5") (pinfunction "CC2_B5") (pintype "bidirectional"))
      (node (ref "R37") (pin "2") (pinfunction "2_2") (pintype "passive"))
    )
    (net (code "64") (name "Net-(J5-CC1)") (class "Default")
      (node (ref "J5") (pin "A5") (pinfunction "CC1_A5") (pintype "bidirectional"))
      (node (ref "R17") (pin "2") (pinfunction "2_2") (pintype "passive"))
    )
    (net (code "65") (name "Net-(J5-CC2)") (class "Default")
      (node (ref "J5") (pin "B5") (pinfunction "CC2_B5") (pintype "bidirectional"))
      (node (ref "R16") (pin "2") (pinfunction "2_2") (pintype "passive"))
    )
    (net (code "66") (name "Net-(J7-2)") (class "Default")
      (node (ref "D7") (pin "C") (pinfunction "C_C") (pintype "passive"))
      (node (ref "J7") (pin "1") (pinfunction "2_1") (pintype "passive"))
    )
    (net (code "67") (name "Net-(JP9-Pad1)") (class "Default")
      (node (ref "JP9") (pin "1") (pinfunction "1_1") (pintype "passive"))
      (node (ref "R21") (pin "2") (pinfunction "2_2") (pintype "passive"))
    )
    (net (code "68") (name "Net-(JP9-Pad3)") (class "Default")
      (node (ref "JP9") (pin "3") (pinfunction "3_3") (pintype "passive"))
      (node (ref "R22") (pin "2") (pinfunction "2_2") (pintype "passive"))
    )
    (net (code "69") (name "Net-(LED1-PadA)") (class "Default")
      (node (ref "LED1") (pin "A") (pinfunction "A_A") (pintype "passive"))
      (node (ref "R36") (pin "1") (pinfunction "1_1") (pintype "passive"))
    )
    (net (code "70") (name "Net-(LED2-PadA)") (class "Default")
      (node (ref "LED2") (pin "A") (pinfunction "A_A") (pintype "passive"))
      (node (ref "R1") (pin "1") (pinfunction "1_1") (pintype "passive"))
    )
    (net (code "71") (name "Net-(Q2A-B)") (class "Default")
      (node (ref "Q2") (pin "5") (pinfunction "B_5") (pintype "passive"))
      (node (ref "R23") (pin "2") (pinfunction "2_2") (pintype "passive"))
    )
    (net (code "72") (name "Net-(Q2A-E)") (class "Default")
      (node (ref "Q2") (pin "4") (pinfunction "E_4") (pintype "passive"))
      (node (ref "R29") (pin "1") (pinfunction "1_1") (pintype "passive"))
      (node (ref "U6") (pin "14") (pinfunction "~{RTS}_14") (pintype "bidirectional"))
    )
    (net (code "73") (name "Net-(Q2B-B)") (class "Default")
      (node (ref "Q2") (pin "2") (pinfunction "B_2") (pintype "passive"))
      (node (ref "R29") (pin "2") (pinfunction "2_2") (pintype "passive"))
    )
    (net (code "74") (name "Net-(Q2B-E)") (class "Default")
      (node (ref "Q2") (pin "1") (pinfunction "E_1") (pintype "passive"))
      (node (ref "R23") (pin "1") (pinfunction "1_1") (pintype "passive"))
      (node (ref "U6") (pin "13") (pinfunction "~{DTR}_13") (pintype "bidirectional"))
    )
    (net (code "75") (name "Net-(R2A-1)") (class "Default")
      (node (ref "R2") (pin "P1") (pinfunction "1_P1") (pintype "passive"))
      (node (ref "U3") (pin "53") (pinfunction "TIMEPULSE_53") (pintype "bidirectional"))
    )
    (net (code "76") (name "Net-(R2C-1)") (class "Default")
      (node (ref "R2") (pin "P3") (pinfunction "1_P3") (pintype "passive"))
      (node (ref "U3") (pin "50") (pinfunction "~{SAFEBOOT}_50") (pintype "bidirectional"))
    )
    (net (code "77") (name "Net-(R2D-1)") (class "Default")
      (node (ref "R2") (pin "P4") (pinfunction "1_P4") (pintype "passive"))
      (node (ref "U3") (pin "49") (pinfunction "~{RESET}_49") (pintype "bidirectional"))
    )
    (net (code "78") (name "Net-(R9A-1)") (class "Default")
      (node (ref "R9") (pin "P1") (pinfunction "1_P1") (pintype "passive"))
      (node (ref "U3") (pin "46") (pinfunction "TX_READY_46") (pintype "bidirectional"))
    )
    (net (code "79") (name "Net-(R9B-1)") (class "Default")
      (node (ref "R9") (pin "P2") (pinfunction "1_P2") (pintype "passive"))
      (node (ref "U3") (pin "45") (pinfunction "SCL/CLK_45") (pintype "bidirectional"))
    )
    (net (code "80") (name "Net-(R9C-1)") (class "Default")
      (node (ref "R9") (pin "P3") (pinfunction "1_P3") (pintype "passive"))
      (node (ref "U3") (pin "44") (pinfunction "SDA/~{CS}_44") (pintype "bidirectional"))
    )
    (net (code "81") (name "Net-(R9D-1)") (class "Default")
      (node (ref "R9") (pin "P4") (pinfunction "1_P4") (pintype "passive"))
      (node (ref "U3") (pin "43") (pinfunction "RX/MOSI_43") (pintype "bidirectional"))
    )
    (net (code "82") (name "Net-(U1-PROG)") (class "Default")
      (node (ref "R7") (pin "2") (pinfunction "2_2") (pintype "passive"))
      (node (ref "U1") (pin "5") (pinfunction "PROG_5") (pintype "input"))
    )
    (net (code "83") (name "Net-(U1-STAT)") (class "Default")
      (node (ref "R8") (pin "1") (pinfunction "1_1") (pintype "passive"))
      (node (ref "U1") (pin "1") (pinfunction "STAT_1") (pintype "output"))
    )
    (net (code "84") (name "Net-(U3-GEO_STAT)") (class "Default")
      (node (ref "R19") (pin "1") (pinfunction "1_1") (pintype "passive"))
      (node (ref "U3") (pin "19") (pinfunction "GEO_STAT_19") (pintype "bidirectional"))
    )
    (net (code "85") (name "Net-(U3-RTK_STAT)") (class "Default")
      (node (ref "R18") (pin "1") (pinfunction "1_1") (pintype "passive"))
      (node (ref "U3") (pin "20") (pinfunction "RTK_STAT_20") (pintype "bidirectional"))
    )
    (net (code "86") (name "Net-(U3-RX2)") (class "Default")
      (node (ref "R6") (pin "1") (pinfunction "1_1") (pintype "passive"))
      (node (ref "U3") (pin "26") (pinfunction "RX2_26") (pintype "bidirectional"))
    )
    (net (code "87") (name "Net-(U3-TX2)") (class "Default")
      (node (ref "R4") (pin "1") (pinfunction "1_1") (pintype "passive"))
      (node (ref "U3") (pin "27") (pinfunction "TX2_27") (pintype "bidirectional"))
    )
    (net (code "88") (name "Net-(U3-TX{slash}MISO)") (class "Default")
      (node (ref "R3") (pin "1") (pinfunction "1_1") (pintype "passive"))
      (node (ref "U3") (pin "42") (pinfunction "TX/MISO_42") (pintype "bidirectional"))
    )
    (net (code "89") (name "Net-(U3-USB_D+)") (class "Default")
      (node (ref "R27") (pin "2") (pinfunction "2_2") (pintype "passive"))
      (node (ref "U3") (pin "40") (pinfunction "USB_D+_40") (pintype "bidirectional"))
    )
    (net (code "90") (name "Net-(U3-USB_D-)") (class "Default")
      (node (ref "R28") (pin "2") (pinfunction "2_2") (pintype "passive"))
      (node (ref "U3") (pin "39") (pinfunction "USB_D-_39") (pintype "bidirectional"))
    )
    (net (code "91") (name "Net-(U3-V_RF)") (class "Default")
      (node (ref "R14") (pin "2") (pinfunction "2_2") (pintype "passive"))
      (node (ref "U3") (pin "7") (pinfunction "V_RF_7") (pintype "bidirectional"))
    )
    (net (code "92") (name "Net-(U6-UD+)") (class "Default")
      (node (ref "J3") (pin "A6") (pinfunction "D+_A6") (pintype "bidirectional"))
      (node (ref "J3") (pin "B6") (pinfunction "D+_B6") (pintype "bidirectional"))
      (node (ref "U6") (pin "5") (pinfunction "UD+_5") (pintype "bidirectional"))
    )
    (net (code "93") (name "Net-(U6-UD-)") (class "Default")
      (node (ref "J3") (pin "A7") (pinfunction "D-_A7") (pintype "bidirectional"))
      (node (ref "J3") (pin "B7") (pinfunction "D-_B7") (pintype "bidirectional"))
      (node (ref "U6") (pin "6") (pinfunction "UD-_6") (pintype "bidirectional"))
    )
    (net (code "94") (name "PPS_STAT") (class "Default")
      (node (ref "J1") (pin "3") (pinfunction "3_3") (pintype "passive"))
      (node (ref "R11") (pin "2") (pinfunction "2_2") (pintype "passive"))
      (node (ref "R2") (pin "P8") (pinfunction "2_P8") (pintype "passive"))
    )
    (net (code "95") (name "RTK_STAT") (class "Default")
      (node (ref "J1") (pin "4") (pinfunction "4_4") (pintype "passive"))
      (node (ref "R12") (pin "2") (pinfunction "2_2") (pintype "passive"))
      (node (ref "R18") (pin "2") (pinfunction "2_2") (pintype "passive"))
    )
    (net (code "96") (name "SCL") (class "Default")
      (node (ref "J4") (pin "4") (pinfunction "4_4") (pintype "passive"))
      (node (ref "R9") (pin "P7") (pinfunction "2_P7") (pintype "passive"))
    )
    (net (code "97") (name "SDA") (class "Default")
      (node (ref "J4") (pin "3") (pinfunction "3_3") (pintype "passive"))
      (node (ref "R9") (pin "P6") (pinfunction "2_P6") (pintype "passive"))
    )
    (net (code "98") (name "SHLD") (class "Default")
      (node (ref "J3") (pin "SHLD1") (pinfunction "SHLD_SHLD1") (pintype "bidirectional"))
      (node (ref "J3") (pin "SHLD2") (pinfunction "SHLD_SHLD2") (pintype "bidirectional"))
      (node (ref "J3") (pin "SHLD3") (pinfunction "SHLD_SHLD3") (pintype "bidirectional"))
      (node (ref "J3") (pin "SHLD4") (pinfunction "SHLD_SHLD4") (pintype "bidirectional"))
    )
    (net (code "99") (name "TX_READY") (class "Default")
      (node (ref "J1") (pin "2") (pinfunction "2_2") (pintype "passive"))
      (node (ref "R9") (pin "P8") (pinfunction "2_P8") (pintype "passive"))
    )
    (net (code "100") (name "V_BATT") (class "Default")
      (node (ref "C8") (pin "1") (pinfunction "1_1") (pintype "passive"))
      (node (ref "D7") (pin "A") (pinfunction "A_A") (pintype "passive"))
      (node (ref "J10") (pin "1") (pinfunction "1_1") (pintype "passive"))
      (node (ref "J8") (pin "2") (pinfunction "+_2") (pintype "bidirectional"))
      (node (ref "U1") (pin "3") (pinfunction "VBAT_3") (pintype "power_in"))
    )
    (net (code "101") (name "ZED-RXI1") (class "Default")
      (node (ref "R9") (pin "P5") (pinfunction "2_P5") (pintype "passive"))
      (node (ref "SERIAL1_CONNECTION") (pin "2") (pinfunction "2_2") (pintype "bidirectional"))
    )
    (net (code "102") (name "ZED-RXI2") (class "Default")
      (node (ref "BLUETOOTH_BROADCAST") (pin "3") (pinfunction "3_3") (pintype "bidirectional"))
      (node (ref "R6") (pin "2") (pinfunction "2_2") (pintype "passive"))
    )
    (net (code "103") (name "ZED-TXO1") (class "Default")
      (node (ref "R3") (pin "2") (pinfunction "2_2") (pintype "passive"))
      (node (ref "SERIAL1_CONNECTION") (pin "5") (pinfunction "5_5") (pintype "bidirectional"))
    )
    (net (code "104") (name "ZED-TXO2") (class "Default")
      (node (ref "BLUETOOTH_BROADCAST") (pin "6") (pinfunction "6_6") (pintype "bidirectional"))
      (node (ref "R4") (pin "2") (pinfunction "2_2") (pintype "passive"))
    )
    (net (code "105") (name "unconnected-(J8-PAD1-PadNC1)") (class "Default")
      (node (ref "J8") (pin "NC1") (pinfunction "PAD1_NC1") (pintype "bidirectional"))
    )
    (net (code "106") (name "unconnected-(J8-PAD2-PadNC2)") (class "Default")
      (node (ref "J8") (pin "NC2") (pinfunction "PAD2_NC2") (pintype "bidirectional"))
    )
    (net (code "107") (name "unconnected-(U2-NC-Pad4)") (class "Default")
      (node (ref "U2") (pin "4") (pinfunction "NC_4") (pintype "no_connect"))
    )
    (net (code "108") (name "unconnected-(U3-ANT_DETECT-Pad4)") (class "Default")
      (node (ref "U3") (pin "4") (pinfunction "ANT_DETECT_4") (pintype "bidirectional"))
    )
    (net (code "109") (name "unconnected-(U3-ANT_OFF-Pad5)") (class "Default")
      (node (ref "U3") (pin "5") (pinfunction "ANT_OFF_5") (pintype "bidirectional"))
    )
    (net (code "110") (name "unconnected-(U3-D_SEL-Pad47)") (class "Default")
      (node (ref "U3") (pin "47") (pinfunction "D_SEL_47") (pintype "bidirectional"))
    )
    (net (code "111") (name "unconnected-(U3-EXTINT-Pad51)") (class "Default")
      (node (ref "U3") (pin "51") (pinfunction "EXTINT_51") (pintype "bidirectional"))
    )
    (net (code "112") (name "unconnected-(U3-~{ANT_SHORT}-Pad6)") (class "Default")
      (node (ref "U3") (pin "6") (pinfunction "~{ANT_SHORT}_6") (pintype "bidirectional"))
    )
    (net (code "113") (name "unconnected-(U5-SCK{slash}IO6-Pad20)") (class "Default")
      (node (ref "U5") (pin "20") (pinfunction "SCK/IO6_20") (pintype "bidirectional"))
    )
    (net (code "114") (name "unconnected-(U5-SCS{slash}IO11-Pad19)") (class "Default")
      (node (ref "U5") (pin "19") (pinfunction "SCS/IO11_19") (pintype "bidirectional"))
    )
    (net (code "115") (name "unconnected-(U5-SDI{slash}IO8-Pad22)") (class "Default")
      (node (ref "U5") (pin "22") (pinfunction "SDI/IO8_22") (pintype "bidirectional"))
    )
    (net (code "116") (name "unconnected-(U5-SDO{slash}IO7-Pad21)") (class "Default")
      (node (ref "U5") (pin "21") (pinfunction "SDO/IO7_21") (pintype "bidirectional"))
    )
    (net (code "117") (name "unconnected-(U5-SHD{slash}IO9-Pad17)") (class "Default")
      (node (ref "U5") (pin "17") (pinfunction "SHD/IO9_17") (pintype "bidirectional"))
    )
    (net (code "118") (name "unconnected-(U5-SWP{slash}IO10-Pad18)") (class "Default")
      (node (ref "U5") (pin "18") (pinfunction "SWP/IO10_18") (pintype "bidirectional"))
    )
    (net (code "119") (name "unconnected-(U6-R232-Pad15)") (class "Default")
      (node (ref "U6") (pin "15") (pinfunction "R232_15") (pintype "bidirectional"))
    )
    (net (code "120") (name "unconnected-(U6-~{CTS}-Pad9)") (class "Default")
      (node (ref "U6") (pin "9") (pinfunction "~{CTS}_9") (pintype "bidirectional"))
    )
    (net (code "121") (name "unconnected-(U6-~{DCD}-Pad12)") (class "Default")
      (node (ref "U6") (pin "12") (pinfunction "~{DCD}_12") (pintype "bidirectional"))
    )
    (net (code "122") (name "unconnected-(U6-~{DSR}-Pad10)") (class "Default")
      (node (ref "U6") (pin "10") (pinfunction "~{DSR}_10") (pintype "bidirectional"))
    )
    (net (code "123") (name "unconnected-(U6-~{RI}-Pad11)") (class "Default")
      (node (ref "U6") (pin "11") (pinfunction "~{RI}_11") (pintype "bidirectional"))
    )
    (net (code "124") (name "~{RESET}") (class "Default")
      (node (ref "J1") (pin "6") (pinfunction "6_6") (pintype "passive"))
      (node (ref "R2") (pin "P5") (pinfunction "2_P5") (pintype "passive"))
    )
    (net (code "125") (name "~{SAFE}") (class "Default")
      (node (ref "J1") (pin "7") (pinfunction "7_7") (pintype "passive"))
      (node (ref "R2") (pin "P6") (pinfunction "2_P6") (pintype "passive"))
    )
  )
)
